# Coprocessor_Board.net
KiCad netlist of a schematic drawn in EAGLE
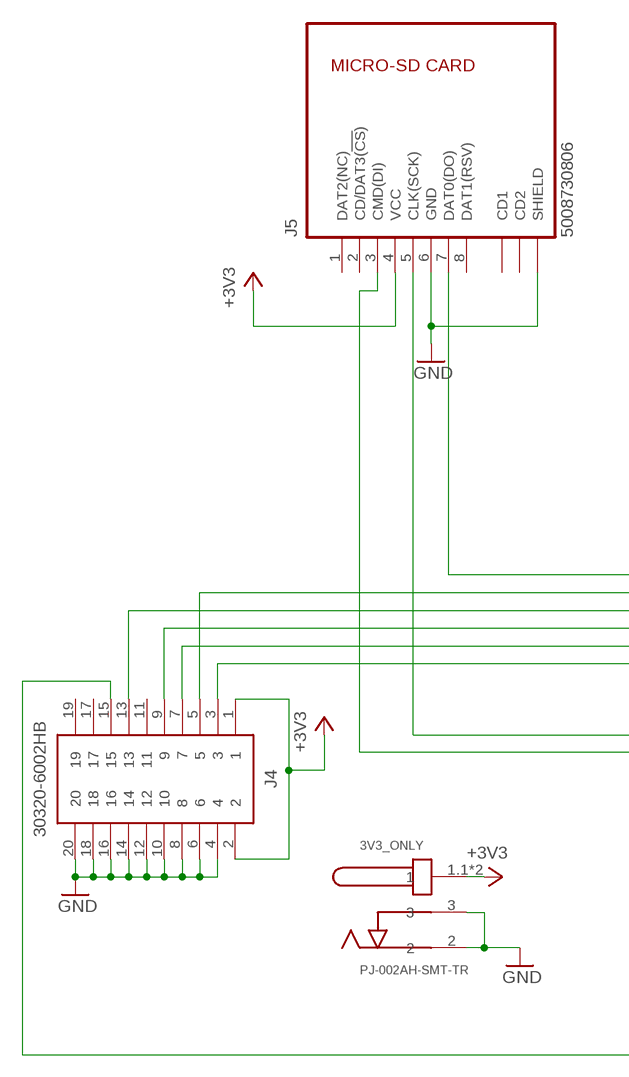
[diagram p0: schematic, sheet 1, part 1 of 2]
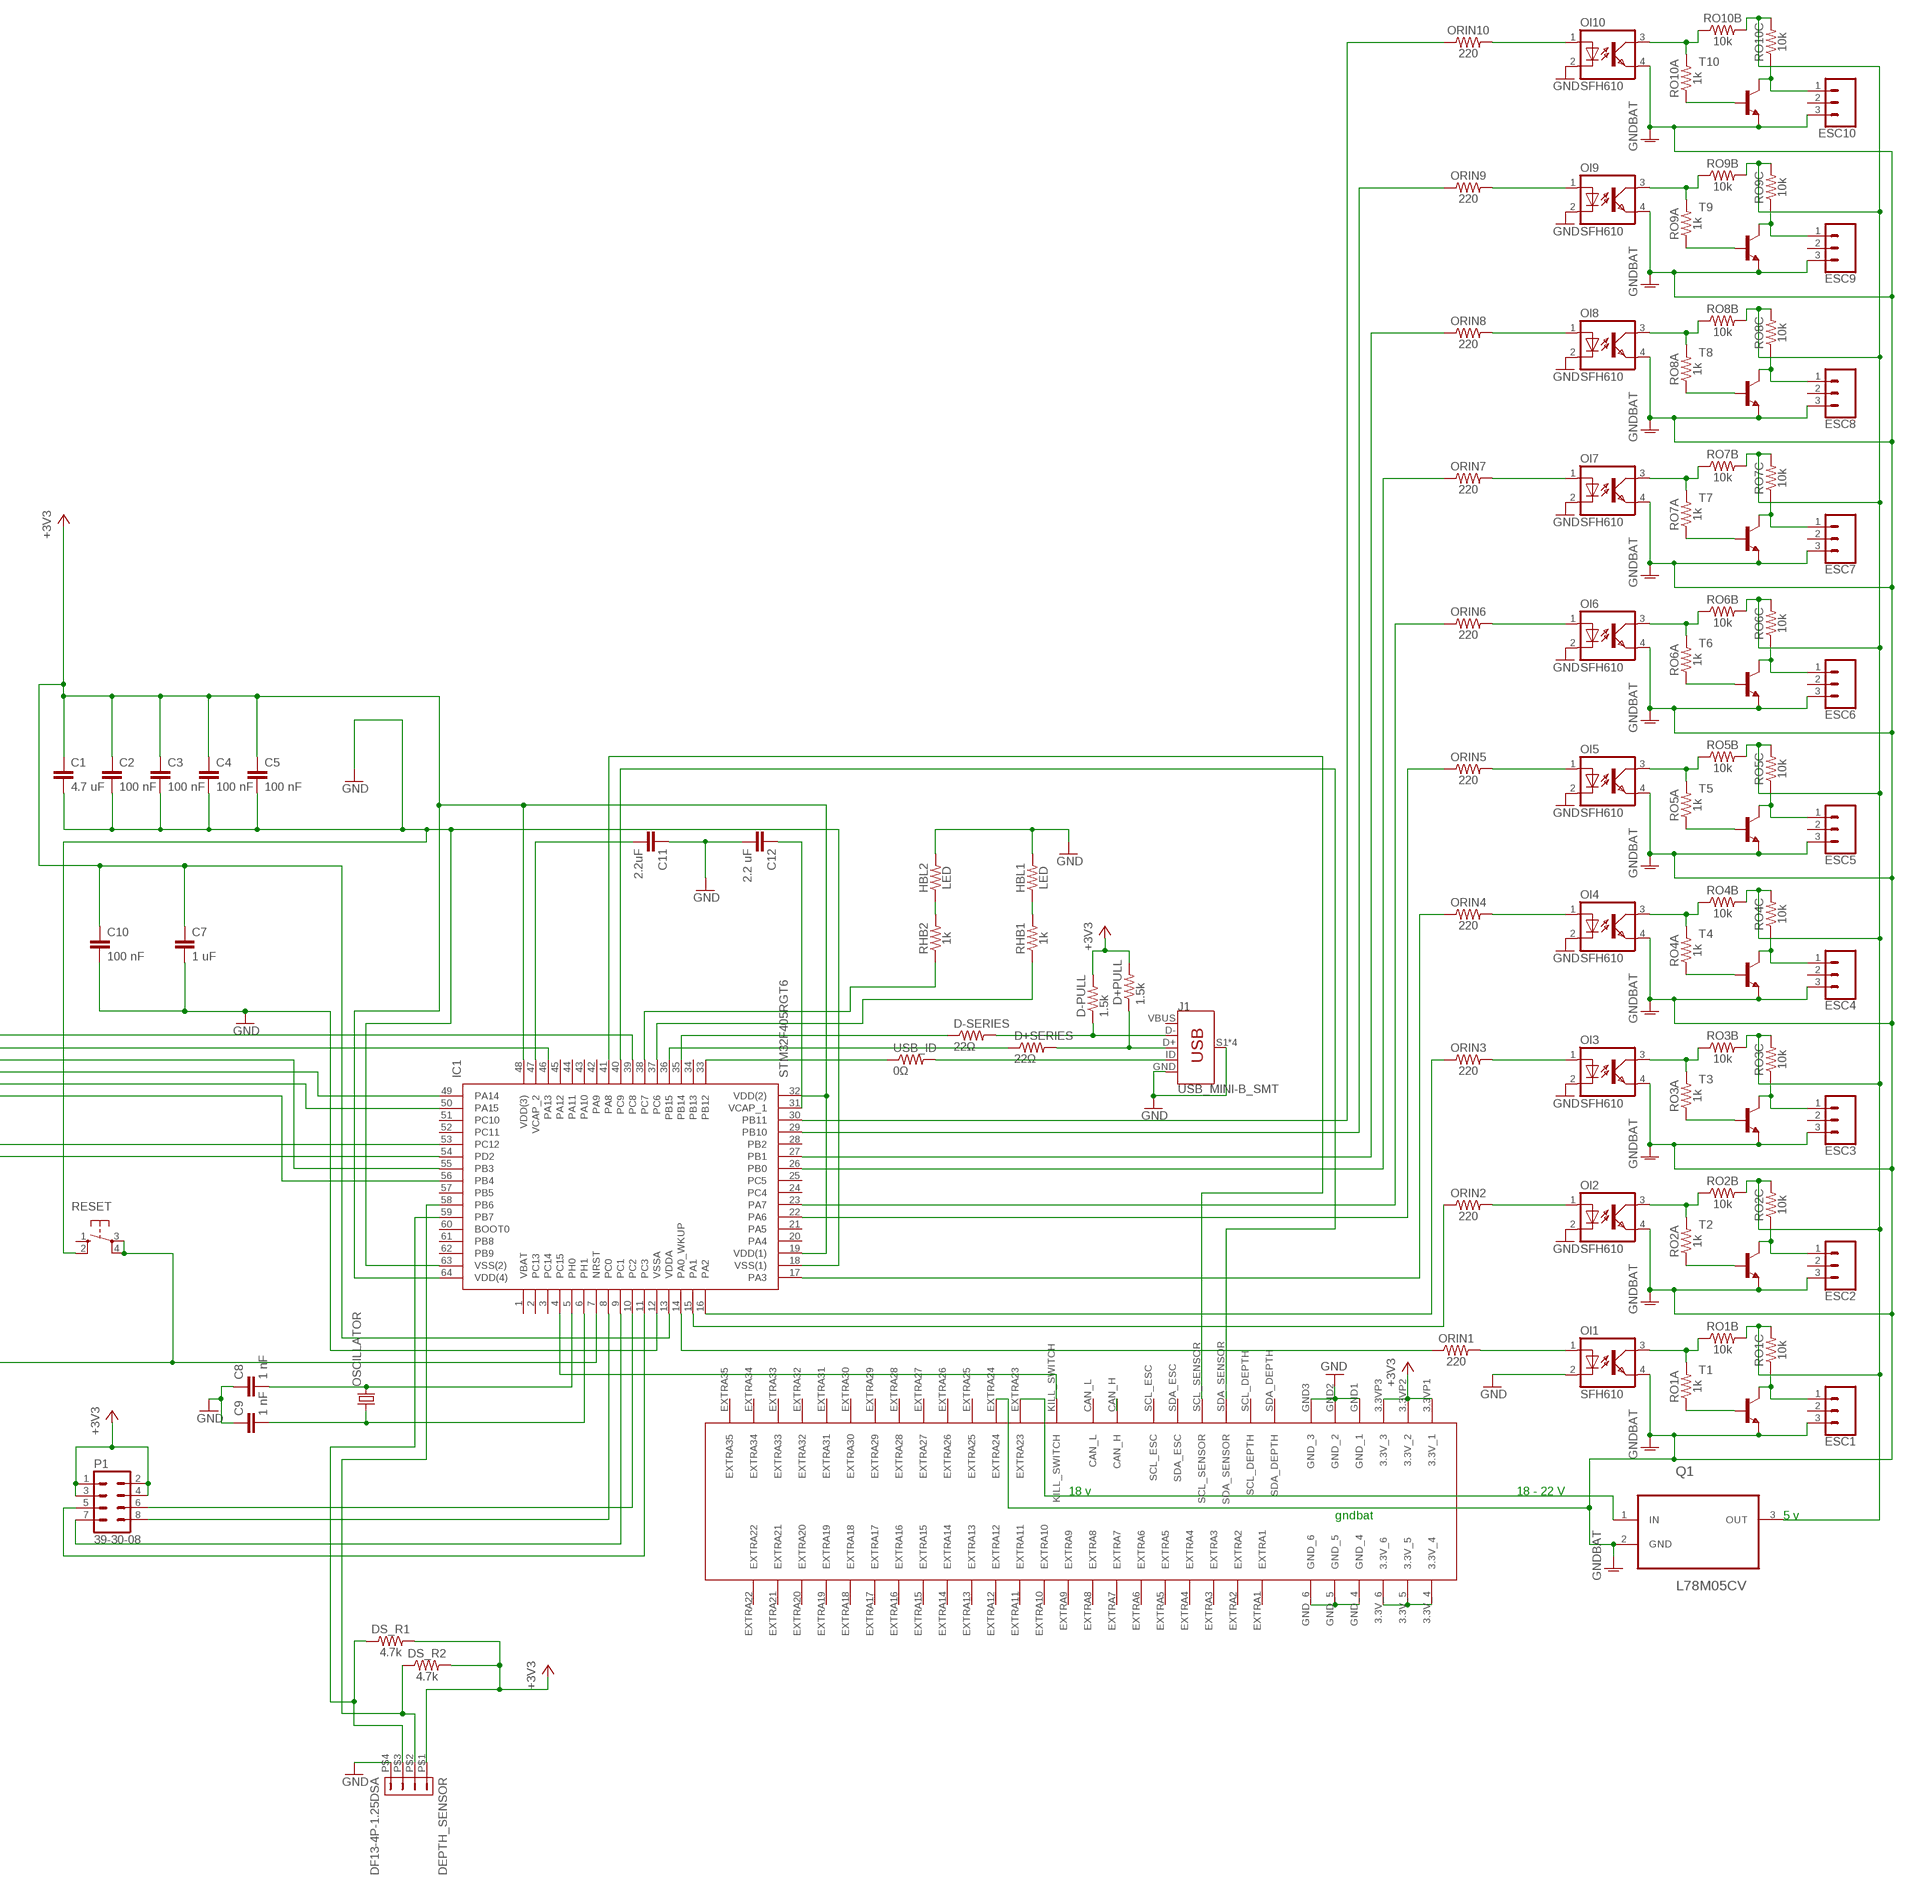
[diagram p1: schematic, sheet 1, part 2 of 2]

(export (version "E")
  (design (tool "Eeschema 10.0.6"))
  (components
    (comp (ref "3V3_ONLY")
      (value "PJ-002AH-SMT-TR")
      (footprint "eagle-import:CUI_PJ-002AH-SMT-TR")
      (fields (field (name "MF") "CUI"))
      (libsource (lib "eagle-import") (part "PJ-002AH-SMT-TR"))
    )
    (comp (ref "C1")
      (value "4.7 uF")
      (footprint "eagle-import:0603")
      (libsource (lib "eagle-import") (part "0.1UF-0603-100V-10%"))
    )
    (comp (ref "C2")
      (value "100 nF")
      (footprint "eagle-import:0603")
      (libsource (lib "eagle-import") (part "0.1UF-0603-100V-10%"))
    )
    (comp (ref "C3")
      (value "100 nF")
      (footprint "eagle-import:0603")
      (libsource (lib "eagle-import") (part "0.1UF-0603-100V-10%"))
    )
    (comp (ref "C4")
      (value "100 nF")
      (footprint "eagle-import:0603")
      (libsource (lib "eagle-import") (part "0.1UF-0603-100V-10%"))
    )
    (comp (ref "C5")
      (value "100 nF")
      (footprint "eagle-import:0603")
      (libsource (lib "eagle-import") (part "0.1UF-0603-100V-10%"))
    )
    (comp (ref "C7")
      (value "1 uF")
      (footprint "eagle-import:0603")
      (libsource (lib "eagle-import") (part "0.1UF-0603-100V-10%"))
    )
    (comp (ref "C8")
      (value "1 nF")
      (footprint "eagle-import:CAP-PTH-2.54")
      (libsource (lib "eagle-import") (part "22PF-PTH-2.54MM-200V-5%"))
    )
    (comp (ref "C9")
      (value "1 nF")
      (footprint "eagle-import:CAP-PTH-2.54")
      (libsource (lib "eagle-import") (part "22PF-PTH-2.54MM-200V-5%"))
    )
    (comp (ref "C10")
      (value "100 nF")
      (footprint "eagle-import:0603")
      (libsource (lib "eagle-import") (part "0.1UF-0603-100V-10%"))
    )
    (comp (ref "C11")
      (value "2.2uF")
      (footprint "eagle-import:0603")
      (libsource (lib "eagle-import") (part "0.1UF-0603-100V-10%"))
    )
    (comp (ref "C12")
      (value "2.2 uF")
      (footprint "eagle-import:0603")
      (libsource (lib "eagle-import") (part "0.1UF-0603-100V-10%"))
    )
    (comp (ref "D+PULL")
      (value "1.5k")
      (footprint "eagle-import:0204_7")
      (libsource (lib "eagle-import") (part "R-US_0204/7"))
    )
    (comp (ref "D+SERIES")
      (value "22Ω")
      (footprint "eagle-import:0204_7")
      (libsource (lib "eagle-import") (part "R-US_0204/7"))
    )
    (comp (ref "D-PULL")
      (value "1.5k")
      (footprint "eagle-import:0204_7")
      (libsource (lib "eagle-import") (part "R-US_0204/7"))
    )
    (comp (ref "D-SERIES")
      (value "22Ω")
      (footprint "eagle-import:0204_7")
      (libsource (lib "eagle-import") (part "R-US_0204/7"))
    )
    (comp (ref "DEPTH_SENSOR")
      (value "DF13-4P-1.25DSA")
      (footprint "eagle-import:DF13-4P-1.25DSA")
      (libsource (lib "eagle-import") (part "DF13-4P-1.25DSA"))
    )
    (comp (ref "DS_R1")
      (value "4.7k")
      (footprint "eagle-import:AXIAL-0.1")
      (libsource (lib "eagle-import") (part "1KOHM-VERT-1/4W-1%"))
    )
    (comp (ref "DS_R2")
      (value "4.7k")
      (footprint "eagle-import:AXIAL-0.1")
      (libsource (lib "eagle-import") (part "1KOHM-VERT-1/4W-1%"))
    )
    (comp (ref "ESC1")
      (value "CONN_03")
      (footprint "eagle-import:1X03")
      (libsource (lib "eagle-import") (part "CONN_03"))
    )
    (comp (ref "ESC2")
      (value "CONN_03")
      (footprint "eagle-import:1X03")
      (libsource (lib "eagle-import") (part "CONN_03"))
    )
    (comp (ref "ESC3")
      (value "CONN_03")
      (footprint "eagle-import:1X03")
      (libsource (lib "eagle-import") (part "CONN_03"))
    )
    (comp (ref "ESC4")
      (value "CONN_03")
      (footprint "eagle-import:1X03")
      (libsource (lib "eagle-import") (part "CONN_03"))
    )
    (comp (ref "ESC5")
      (value "CONN_03")
      (footprint "eagle-import:1X03")
      (libsource (lib "eagle-import") (part "CONN_03"))
    )
    (comp (ref "ESC6")
      (value "CONN_03")
      (footprint "eagle-import:1X03")
      (libsource (lib "eagle-import") (part "CONN_03"))
    )
    (comp (ref "ESC7")
      (value "CONN_03")
      (footprint "eagle-import:1X03")
      (libsource (lib "eagle-import") (part "CONN_03"))
    )
    (comp (ref "ESC8")
      (value "CONN_03")
      (footprint "eagle-import:1X03")
      (libsource (lib "eagle-import") (part "CONN_03"))
    )
    (comp (ref "ESC9")
      (value "CONN_03")
      (footprint "eagle-import:1X03")
      (libsource (lib "eagle-import") (part "CONN_03"))
    )
    (comp (ref "ESC10")
      (value "CONN_03")
      (footprint "eagle-import:1X03")
      (libsource (lib "eagle-import") (part "CONN_03"))
    )
    (comp (ref "HBL1")
      (value "LED")
      (footprint "eagle-import:AXIAL-0.1")
      (libsource (lib "eagle-import") (part "1KOHM-VERT-1/4W-1%"))
    )
    (comp (ref "HBL2")
      (value "LED")
      (footprint "eagle-import:AXIAL-0.1")
      (libsource (lib "eagle-import") (part "1KOHM-VERT-1/4W-1%"))
    )
    (comp (ref "IC1")
      (value "STM32F405RGT6")
      (footprint "eagle-import:QFP50P1200X1200X160-64N")
      (fields (field (name "RS_PART_NUMBER") "7468217"))
      (libsource (lib "eagle-import") (part "STM32F405RGT6"))
    )
    (comp (ref "J1")
      (value "USB_MINI-B_SMT")
      (footprint "eagle-import:USB-MINIB")
      (libsource (lib "eagle-import") (part "USB_MINI-B_SMT"))
    )
    (comp (ref "J4")
      (value "30320-6002HB")
      (footprint "eagle-import:SHDR20W81P254_2X10_3300X840X93")
      (fields (field (name "RS_PART_NUMBER") "8273587"))
      (libsource (lib "eagle-import") (part "30320-6002HB"))
    )
    (comp (ref "J5")
      (value "5008730806")
      (footprint "eagle-import:5008730806")
      (fields (field (name "MF") "Molex") (field (name "MP") "500873-0806"))
      (libsource (lib "eagle-import") (part "5008730806"))
    )
    (comp (ref "OI1")
      (value "SFH610")
      (footprint "eagle-import:DIL04")
      (fields (field (name "MF") "VISHAY/TELEFUNKEN") (field (name "MPN") "SFH6106-4"))
      (libsource (lib "eagle-import") (part "SFH610"))
    )
    (comp (ref "OI2")
      (value "SFH610")
      (footprint "eagle-import:DIL04")
      (fields (field (name "MF") "VISHAY/TELEFUNKEN") (field (name "MPN") "SFH6106-4"))
      (libsource (lib "eagle-import") (part "SFH610"))
    )
    (comp (ref "OI3")
      (value "SFH610")
      (footprint "eagle-import:DIL04")
      (fields (field (name "MF") "VISHAY/TELEFUNKEN") (field (name "MPN") "SFH6106-4"))
      (libsource (lib "eagle-import") (part "SFH610"))
    )
    (comp (ref "OI4")
      (value "SFH610")
      (footprint "eagle-import:DIL04")
      (fields (field (name "MF") "VISHAY/TELEFUNKEN") (field (name "MPN") "SFH6106-4"))
      (libsource (lib "eagle-import") (part "SFH610"))
    )
    (comp (ref "OI5")
      (value "SFH610")
      (footprint "eagle-import:DIL04")
      (fields (field (name "MF") "VISHAY/TELEFUNKEN") (field (name "MPN") "SFH6106-4"))
      (libsource (lib "eagle-import") (part "SFH610"))
    )
    (comp (ref "OI6")
      (value "SFH610")
      (footprint "eagle-import:DIL04")
      (fields (field (name "MF") "VISHAY/TELEFUNKEN") (field (name "MPN") "SFH6106-4"))
      (libsource (lib "eagle-import") (part "SFH610"))
    )
    (comp (ref "OI7")
      (value "SFH610")
      (footprint "eagle-import:DIL04")
      (fields (field (name "MF") "VISHAY/TELEFUNKEN") (field (name "MPN") "SFH6106-4"))
      (libsource (lib "eagle-import") (part "SFH610"))
    )
    (comp (ref "OI8")
      (value "SFH610")
      (footprint "eagle-import:DIL04")
      (fields (field (name "MF") "VISHAY/TELEFUNKEN") (field (name "MPN") "SFH6106-4"))
      (libsource (lib "eagle-import") (part "SFH610"))
    )
    (comp (ref "OI9")
      (value "SFH610")
      (footprint "eagle-import:DIL04")
      (fields (field (name "MF") "VISHAY/TELEFUNKEN") (field (name "MPN") "SFH6106-4"))
      (libsource (lib "eagle-import") (part "SFH610"))
    )
    (comp (ref "OI10")
      (value "SFH610")
      (footprint "eagle-import:DIL04")
      (fields (field (name "MF") "VISHAY/TELEFUNKEN") (field (name "MPN") "SFH6106-4"))
      (libsource (lib "eagle-import") (part "SFH610"))
    )
    (comp (ref "ORIN1")
      (value "220")
      (footprint "eagle-import:AXIAL-0.1")
      (libsource (lib "eagle-import") (part "1KOHM-VERT-1/4W-1%"))
    )
    (comp (ref "ORIN2")
      (value "220")
      (footprint "eagle-import:AXIAL-0.1")
      (libsource (lib "eagle-import") (part "1KOHM-VERT-1/4W-1%"))
    )
    (comp (ref "ORIN3")
      (value "220")
      (footprint "eagle-import:AXIAL-0.1")
      (libsource (lib "eagle-import") (part "1KOHM-VERT-1/4W-1%"))
    )
    (comp (ref "ORIN4")
      (value "220")
      (footprint "eagle-import:AXIAL-0.1")
      (libsource (lib "eagle-import") (part "1KOHM-VERT-1/4W-1%"))
    )
    (comp (ref "ORIN5")
      (value "220")
      (footprint "eagle-import:AXIAL-0.1")
      (libsource (lib "eagle-import") (part "1KOHM-VERT-1/4W-1%"))
    )
    (comp (ref "ORIN6")
      (value "220")
      (footprint "eagle-import:AXIAL-0.1")
      (libsource (lib "eagle-import") (part "1KOHM-VERT-1/4W-1%"))
    )
    (comp (ref "ORIN7")
      (value "220")
      (footprint "eagle-import:AXIAL-0.1")
      (libsource (lib "eagle-import") (part "1KOHM-VERT-1/4W-1%"))
    )
    (comp (ref "ORIN8")
      (value "220")
      (footprint "eagle-import:AXIAL-0.1")
      (libsource (lib "eagle-import") (part "1KOHM-VERT-1/4W-1%"))
    )
    (comp (ref "ORIN9")
      (value "220")
      (footprint "eagle-import:AXIAL-0.1")
      (libsource (lib "eagle-import") (part "1KOHM-VERT-1/4W-1%"))
    )
    (comp (ref "ORIN10")
      (value "220")
      (footprint "eagle-import:AXIAL-0.1")
      (libsource (lib "eagle-import") (part "1KOHM-VERT-1/4W-1%"))
    )
    (comp (ref "OSCILLATOR")
      (value "CRYSTALHC49S")
      (footprint "eagle-import:HC49_S")
      (libsource (lib "eagle-import") (part "CRYSTALHC49S"))
    )
    (comp (ref "P1")
      (value "39-30-08")
      (footprint "eagle-import:39-30-_08_")
      (libsource (lib "eagle-import") (part "39-30-?08?"))
    )
    (comp (ref "Q1")
      (value "L78M05CV")
      (footprint "eagle-import:TO254P450X1020X1935-3P")
      (fields (field (name "MF") "STMicroelectronics"))
      (libsource (lib "eagle-import") (part "L78M05CV"))
    )
    (comp (ref "RESET")
      (value "10-XX")
      (footprint "eagle-import:B3F-10XX")
      (fields (field (name "MPN") "B3F-1000"))
      (libsource (lib "eagle-import") (part "10-XX"))
    )
    (comp (ref "RHB1")
      (value "1k")
      (footprint "eagle-import:AXIAL-0.3")
      (libsource (lib "eagle-import") (part "1KOHM-HORIZ-1/4W-1%"))
    )
    (comp (ref "RHB2")
      (value "1k")
      (footprint "eagle-import:AXIAL-0.3")
      (libsource (lib "eagle-import") (part "1KOHM-HORIZ-1/4W-5%"))
    )
    (comp (ref "RO1A")
      (value "1k")
      (footprint "eagle-import:0603")
      (libsource (lib "eagle-import") (part "1KOHM-0603-1/10W-1%"))
    )
    (comp (ref "RO1B")
      (value "10k")
      (footprint "eagle-import:0603")
      (libsource (lib "eagle-import") (part "1KOHM-0603-1/10W-1%"))
    )
    (comp (ref "RO1C")
      (value "10k")
      (footprint "eagle-import:0603")
      (libsource (lib "eagle-import") (part "1KOHM-0603-1/10W-1%"))
    )
    (comp (ref "RO2A")
      (value "1k")
      (footprint "eagle-import:0603")
      (libsource (lib "eagle-import") (part "1KOHM-0603-1/10W-1%"))
    )
    (comp (ref "RO2B")
      (value "10k")
      (footprint "eagle-import:0603")
      (libsource (lib "eagle-import") (part "1KOHM-0603-1/10W-1%"))
    )
    (comp (ref "RO2C")
      (value "10k")
      (footprint "eagle-import:0603")
      (libsource (lib "eagle-import") (part "1KOHM-0603-1/10W-1%"))
    )
    (comp (ref "RO3A")
      (value "1k")
      (footprint "eagle-import:0603")
      (libsource (lib "eagle-import") (part "1KOHM-0603-1/10W-1%"))
    )
    (comp (ref "RO3B")
      (value "10k")
      (footprint "eagle-import:0603")
      (libsource (lib "eagle-import") (part "1KOHM-0603-1/10W-1%"))
    )
    (comp (ref "RO3C")
      (value "10k")
      (footprint "eagle-import:0603")
      (libsource (lib "eagle-import") (part "1KOHM-0603-1/10W-1%"))
    )
    (comp (ref "RO4A")
      (value "1k")
      (footprint "eagle-import:0603")
      (libsource (lib "eagle-import") (part "1KOHM-0603-1/10W-1%"))
    )
    (comp (ref "RO4B")
      (value "10k")
      (footprint "eagle-import:0603")
      (libsource (lib "eagle-import") (part "1KOHM-0603-1/10W-1%"))
    )
    (comp (ref "RO4C")
      (value "10k")
      (footprint "eagle-import:0603")
      (libsource (lib "eagle-import") (part "1KOHM-0603-1/10W-1%"))
    )
    (comp (ref "RO5A")
      (value "1k")
      (footprint "eagle-import:0603")
      (libsource (lib "eagle-import") (part "1KOHM-0603-1/10W-1%"))
    )
    (comp (ref "RO5B")
      (value "10k")
      (footprint "eagle-import:0603")
      (libsource (lib "eagle-import") (part "1KOHM-0603-1/10W-1%"))
    )
    (comp (ref "RO5C")
      (value "10k")
      (footprint "eagle-import:0603")
      (libsource (lib "eagle-import") (part "1KOHM-0603-1/10W-1%"))
    )
    (comp (ref "RO6A")
      (value "1k")
      (footprint "eagle-import:0603")
      (libsource (lib "eagle-import") (part "1KOHM-0603-1/10W-1%"))
    )
    (comp (ref "RO6B")
      (value "10k")
      (footprint "eagle-import:0603")
      (libsource (lib "eagle-import") (part "1KOHM-0603-1/10W-1%"))
    )
    (comp (ref "RO6C")
      (value "10k")
      (footprint "eagle-import:0603")
      (libsource (lib "eagle-import") (part "1KOHM-0603-1/10W-1%"))
    )
    (comp (ref "RO7A")
      (value "1k")
      (footprint "eagle-import:0603")
      (libsource (lib "eagle-import") (part "1KOHM-0603-1/10W-1%"))
    )
    (comp (ref "RO7B")
      (value "10k")
      (footprint "eagle-import:0603")
      (libsource (lib "eagle-import") (part "1KOHM-0603-1/10W-1%"))
    )
    (comp (ref "RO7C")
      (value "10k")
      (footprint "eagle-import:0603")
      (libsource (lib "eagle-import") (part "1KOHM-0603-1/10W-1%"))
    )
    (comp (ref "RO8A")
      (value "1k")
      (footprint "eagle-import:0603")
      (libsource (lib "eagle-import") (part "1KOHM-0603-1/10W-1%"))
    )
    (comp (ref "RO8B")
      (value "10k")
      (footprint "eagle-import:0603")
      (libsource (lib "eagle-import") (part "1KOHM-0603-1/10W-1%"))
    )
    (comp (ref "RO8C")
      (value "10k")
      (footprint "eagle-import:0603")
      (libsource (lib "eagle-import") (part "1KOHM-0603-1/10W-1%"))
    )
    (comp (ref "RO9A")
      (value "1k")
      (footprint "eagle-import:0603")
      (libsource (lib "eagle-import") (part "1KOHM-0603-1/10W-1%"))
    )
    (comp (ref "RO9B")
      (value "10k")
      (footprint "eagle-import:0603")
      (libsource (lib "eagle-import") (part "1KOHM-0603-1/10W-1%"))
    )
    (comp (ref "RO9C")
      (value "10k")
      (footprint "eagle-import:0603")
      (libsource (lib "eagle-import") (part "1KOHM-0603-1/10W-1%"))
    )
    (comp (ref "RO10A")
      (value "1k")
      (footprint "eagle-import:0603")
      (libsource (lib "eagle-import") (part "1KOHM-0603-1/10W-1%"))
    )
    (comp (ref "RO10B")
      (value "10k")
      (footprint "eagle-import:0603")
      (libsource (lib "eagle-import") (part "1KOHM-0603-1/10W-1%"))
    )
    (comp (ref "RO10C")
      (value "10k")
      (footprint "eagle-import:0603")
      (libsource (lib "eagle-import") (part "1KOHM-0603-1/10W-1%"))
    )
    (comp (ref "T1")
      (value "-NPN-TO126V")
      (footprint "eagle-import:TO126V")
      (libsource (lib "eagle-import") (part "-NPN-TO126V"))
    )
    (comp (ref "T2")
      (value "-NPN-TO126V")
      (footprint "eagle-import:TO126V")
      (libsource (lib "eagle-import") (part "-NPN-TO126V"))
    )
    (comp (ref "T3")
      (value "-NPN-TO126V")
      (footprint "eagle-import:TO126V")
      (libsource (lib "eagle-import") (part "-NPN-TO126V"))
    )
    (comp (ref "T4")
      (value "-NPN-TO126V")
      (footprint "eagle-import:TO126V")
      (libsource (lib "eagle-import") (part "-NPN-TO126V"))
    )
    (comp (ref "T5")
      (value "-NPN-TO126V")
      (footprint "eagle-import:TO126V")
      (libsource (lib "eagle-import") (part "-NPN-TO126V"))
    )
    (comp (ref "T6")
      (value "-NPN-TO126V")
      (footprint "eagle-import:TO126V")
      (libsource (lib "eagle-import") (part "-NPN-TO126V"))
    )
    (comp (ref "T7")
      (value "-NPN-TO126V")
      (footprint "eagle-import:TO126V")
      (libsource (lib "eagle-import") (part "-NPN-TO126V"))
    )
    (comp (ref "T8")
      (value "-NPN-TO126V")
      (footprint "eagle-import:TO126V")
      (libsource (lib "eagle-import") (part "-NPN-TO126V"))
    )
    (comp (ref "T9")
      (value "-NPN-TO126V")
      (footprint "eagle-import:TO126V")
      (libsource (lib "eagle-import") (part "-NPN-TO126V"))
    )
    (comp (ref "T10")
      (value "-NPN-TO126V")
      (footprint "eagle-import:TO126V")
      (libsource (lib "eagle-import") (part "-NPN-TO126V"))
    )
    (comp (ref "U$1")
      (value "5530843")
      (footprint "eagle-import:5530843-6-BOARDFINGERS")
      (libsource (lib "eagle-import") (part "5530843"))
    )
    (comp (ref "USB_ID")
      (value "0Ω")
      (footprint "eagle-import:0204_7")
      (libsource (lib "eagle-import") (part "R-US_0204/7"))
    )
  )
  (nets
    (net (code "1") (name "+3V3") (class "Default")
      (node (ref "3V3_ONLY") (pin "1.1") (pinfunction "1_1.1") (pintype "passive"))
      (node (ref "3V3_ONLY") (pin "1.2") (pinfunction "1_1.2") (pintype "passive"))
      (node (ref "C1") (pin "1") (pinfunction "1_1") (pintype "passive"))
      (node (ref "C10") (pin "1") (pinfunction "1_1") (pintype "passive"))
      (node (ref "C2") (pin "1") (pinfunction "1_1") (pintype "passive"))
      (node (ref "C3") (pin "1") (pinfunction "1_1") (pintype "passive"))
      (node (ref "C4") (pin "1") (pinfunction "1_1") (pintype "passive"))
      (node (ref "C5") (pin "1") (pinfunction "1_1") (pintype "passive"))
      (node (ref "C7") (pin "1") (pinfunction "1_1") (pintype "passive"))
      (node (ref "D+PULL") (pin "2") (pinfunction "2_2") (pintype "passive"))
      (node (ref "D-PULL") (pin "2") (pinfunction "2_2") (pintype "passive"))
      (node (ref "DEPTH_SENSOR") (pin "P$1") (pinfunction "1_P$1") (pintype "passive"))
      (node (ref "DS_R1") (pin "P$2") (pinfunction "2_P$2") (pintype "passive"))
      (node (ref "DS_R2") (pin "P$2") (pinfunction "2_P$2") (pintype "passive"))
      (node (ref "IC1") (pin "13") (pinfunction "VDDA_13") (pintype "power_in"))
      (node (ref "IC1") (pin "19") (pinfunction "VDD(1)_19") (pintype "power_in"))
      (node (ref "IC1") (pin "32") (pinfunction "VDD(2)_32") (pintype "power_in"))
      (node (ref "IC1") (pin "48") (pinfunction "VDD(3)_48") (pintype "power_in"))
      (node (ref "IC1") (pin "64") (pinfunction "VDD(4)_64") (pintype "power_in"))
      (node (ref "J4") (pin "1") (pinfunction "1_1") (pintype "passive"))
      (node (ref "J4") (pin "2") (pinfunction "2_2") (pintype "passive"))
      (node (ref "J5") (pin "4") (pinfunction "VCC_4") (pintype "bidirectional"))
      (node (ref "P1") (pin "1") (pinfunction "1_1") (pintype "passive"))
      (node (ref "P1") (pin "2") (pinfunction "2_2") (pintype "passive"))
      (node (ref "P1") (pin "3") (pinfunction "3_3") (pintype "passive"))
      (node (ref "P1") (pin "4") (pinfunction "4_4") (pintype "passive"))
      (node (ref "U$1") (pin "3.3VP1") (pinfunction "3.3V_1_3.3VP1") (pintype "bidirectional"))
      (node (ref "U$1") (pin "3.3VP2") (pinfunction "3.3V_2_3.3VP2") (pintype "bidirectional"))
      (node (ref "U$1") (pin "3.3VP3") (pinfunction "3.3V_3_3.3VP3") (pintype "bidirectional"))
      (node (ref "U$1") (pin "3.3V_4") (pinfunction "3.3V_4_3.3V_4") (pintype "bidirectional"))
      (node (ref "U$1") (pin "3.3V_5") (pinfunction "3.3V_5_3.3V_5") (pintype "bidirectional"))
      (node (ref "U$1") (pin "3.3V_6") (pinfunction "3.3V_6_3.3V_6") (pintype "bidirectional"))
    )
    (net (code "2") (name "/VBUS") (class "Default")
      (node (ref "J1") (pin "VBUS") (pinfunction "VBUS_VBUS") (pintype "power_in"))
    )
    (net (code "3") (name "GND") (class "Default")
      (node (ref "3V3_ONLY") (pin "2") (pinfunction "2_2") (pintype "passive"))
      (node (ref "3V3_ONLY") (pin "3") (pinfunction "3_3") (pintype "passive"))
      (node (ref "C1") (pin "2") (pinfunction "2_2") (pintype "passive"))
      (node (ref "C10") (pin "2") (pinfunction "2_2") (pintype "passive"))
      (node (ref "C11") (pin "1") (pinfunction "1_1") (pintype "passive"))
      (node (ref "C12") (pin "2") (pinfunction "2_2") (pintype "passive"))
      (node (ref "C2") (pin "2") (pinfunction "2_2") (pintype "passive"))
      (node (ref "C3") (pin "2") (pinfunction "2_2") (pintype "passive"))
      (node (ref "C4") (pin "2") (pinfunction "2_2") (pintype "passive"))
      (node (ref "C5") (pin "2") (pinfunction "2_2") (pintype "passive"))
      (node (ref "C7") (pin "2") (pinfunction "2_2") (pintype "passive"))
      (node (ref "C8") (pin "1") (pinfunction "1_1") (pintype "passive"))
      (node (ref "C9") (pin "1") (pinfunction "1_1") (pintype "passive"))
      (node (ref "DEPTH_SENSOR") (pin "P$4") (pinfunction "4_P$4") (pintype "passive"))
      (node (ref "HBL1") (pin "P$2") (pinfunction "2_P$2") (pintype "passive"))
      (node (ref "HBL2") (pin "P$2") (pinfunction "2_P$2") (pintype "passive"))
      (node (ref "IC1") (pin "12") (pinfunction "VSSA_12") (pintype "power_in"))
      (node (ref "IC1") (pin "18") (pinfunction "VSS(1)_18") (pintype "power_in"))
      (node (ref "IC1") (pin "63") (pinfunction "VSS(2)_63") (pintype "power_in"))
      (node (ref "J1") (pin "GND") (pinfunction "GND_GND") (pintype "power_in"))
      (node (ref "J1") (pin "S1") (pinfunction "SHIELD_S1") (pintype "bidirectional"))
      (node (ref "J1") (pin "S2") (pinfunction "SHIELD_S2") (pintype "bidirectional"))
      (node (ref "J1") (pin "S3") (pinfunction "SHIELD_S3") (pintype "bidirectional"))
      (node (ref "J1") (pin "S4") (pinfunction "SHIELD_S4") (pintype "bidirectional"))
      (node (ref "J4") (pin "10") (pinfunction "10_10") (pintype "passive"))
      (node (ref "J4") (pin "12") (pinfunction "12_12") (pintype "passive"))
      (node (ref "J4") (pin "14") (pinfunction "14_14") (pintype "passive"))
      (node (ref "J4") (pin "16") (pinfunction "16_16") (pintype "passive"))
      (node (ref "J4") (pin "18") (pinfunction "18_18") (pintype "passive"))
      (node (ref "J4") (pin "20") (pinfunction "20_20") (pintype "passive"))
      (node (ref "J4") (pin "4") (pinfunction "4_4") (pintype "passive"))
      (node (ref "J4") (pin "6") (pinfunction "6_6") (pintype "passive"))
      (node (ref "J4") (pin "8") (pinfunction "8_8") (pintype "passive"))
      (node (ref "J5") (pin "6") (pinfunction "GND_6") (pintype "bidirectional"))
      (node (ref "J5") (pin "S3") (pinfunction "SHIELD_S3") (pintype "bidirectional"))
      (node (ref "J5") (pin "S4") (pinfunction "SHIELD_S4") (pintype "bidirectional"))
      (node (ref "OI1") (pin "2") (pinfunction "C_2") (pintype "passive"))
      (node (ref "OI10") (pin "2") (pinfunction "C_2") (pintype "passive"))
      (node (ref "OI2") (pin "2") (pinfunction "C_2") (pintype "passive"))
      (node (ref "OI3") (pin "2") (pinfunction "C_2") (pintype "passive"))
      (node (ref "OI4") (pin "2") (pinfunction "C_2") (pintype "passive"))
      (node (ref "OI5") (pin "2") (pinfunction "C_2") (pintype "passive"))
      (node (ref "OI6") (pin "2") (pinfunction "C_2") (pintype "passive"))
      (node (ref "OI7") (pin "2") (pinfunction "C_2") (pintype "passive"))
      (node (ref "OI8") (pin "2") (pinfunction "C_2") (pintype "passive"))
      (node (ref "OI9") (pin "2") (pinfunction "C_2") (pintype "passive"))
      (node (ref "RESET") (pin "2") (pinfunction "S1_2") (pintype "passive"))
      (node (ref "U$1") (pin "GND1") (pinfunction "GND_1_GND1") (pintype "bidirectional"))
      (node (ref "U$1") (pin "GND2") (pinfunction "GND_2_GND2") (pintype "bidirectional"))
      (node (ref "U$1") (pin "GND3") (pinfunction "GND_3_GND3") (pintype "bidirectional"))
      (node (ref "U$1") (pin "GND_4") (pinfunction "GND_4_GND_4") (pintype "bidirectional"))
      (node (ref "U$1") (pin "GND_5") (pinfunction "GND_5_GND_5") (pintype "bidirectional"))
      (node (ref "U$1") (pin "GND_6") (pinfunction "GND_6_GND_6") (pintype "bidirectional"))
    )
    (net (code "4") (name "GNDBAT") (class "Default")
      (node (ref "ESC1") (pin "3") (pinfunction "3_3") (pintype "passive"))
      (node (ref "ESC10") (pin "3") (pinfunction "3_3") (pintype "passive"))
      (node (ref "ESC2") (pin "3") (pinfunction "3_3") (pintype "passive"))
      (node (ref "ESC3") (pin "3") (pinfunction "3_3") (pintype "passive"))
      (node (ref "ESC4") (pin "3") (pinfunction "3_3") (pintype "passive"))
      (node (ref "ESC5") (pin "3") (pinfunction "3_3") (pintype "passive"))
      (node (ref "ESC6") (pin "3") (pinfunction "3_3") (pintype "passive"))
      (node (ref "ESC7") (pin "3") (pinfunction "3_3") (pintype "passive"))
      (node (ref "ESC8") (pin "3") (pinfunction "3_3") (pintype "passive"))
      (node (ref "ESC9") (pin "3") (pinfunction "3_3") (pintype "passive"))
      (node (ref "OI1") (pin "4") (pinfunction "EMIT_4") (pintype "passive"))
      (node (ref "OI10") (pin "4") (pinfunction "EMIT_4") (pintype "passive"))
      (node (ref "OI2") (pin "4") (pinfunction "EMIT_4") (pintype "passive"))
      (node (ref "OI3") (pin "4") (pinfunction "EMIT_4") (pintype "passive"))
      (node (ref "OI4") (pin "4") (pinfunction "EMIT_4") (pintype "passive"))
      (node (ref "OI5") (pin "4") (pinfunction "EMIT_4") (pintype "passive"))
      (node (ref "OI6") (pin "4") (pinfunction "EMIT_4") (pintype "passive"))
      (node (ref "OI7") (pin "4") (pinfunction "EMIT_4") (pintype "passive"))
      (node (ref "OI8") (pin "4") (pinfunction "EMIT_4") (pintype "passive"))
      (node (ref "OI9") (pin "4") (pinfunction "EMIT_4") (pintype "passive"))
      (node (ref "Q1") (pin "2") (pinfunction "GND_2") (pintype "passive"))
      (node (ref "T1") (pin "1") (pinfunction "E_1") (pintype "passive"))
      (node (ref "T10") (pin "1") (pinfunction "E_1") (pintype "passive"))
      (node (ref "T2") (pin "1") (pinfunction "E_1") (pintype "passive"))
      (node (ref "T3") (pin "1") (pinfunction "E_1") (pintype "passive"))
      (node (ref "T4") (pin "1") (pinfunction "E_1") (pintype "passive"))
      (node (ref "T5") (pin "1") (pinfunction "E_1") (pintype "passive"))
      (node (ref "T6") (pin "1") (pinfunction "E_1") (pintype "passive"))
      (node (ref "T7") (pin "1") (pinfunction "E_1") (pintype "passive"))
      (node (ref "T8") (pin "1") (pinfunction "E_1") (pintype "passive"))
      (node (ref "T9") (pin "1") (pinfunction "E_1") (pintype "passive"))
      (node (ref "U$1") (pin "EXTRA24") (pinfunction "EXTRA24_EXTRA24") (pintype "bidirectional"))
    )
    (net (code "5") (name "Net-(D+PULL-Pad1)") (class "Default")
      (node (ref "D+PULL") (pin "1") (pinfunction "1_1") (pintype "passive"))
      (node (ref "D+SERIES") (pin "2") (pinfunction "2_2") (pintype "passive"))
      (node (ref "J1") (pin "D+") (pinfunction "D+_D+") (pintype "bidirectional"))
    )
    (net (code "6") (name "Net-(D-PULL-Pad1)") (class "Default")
      (node (ref "D-PULL") (pin "1") (pinfunction "1_1") (pintype "passive"))
      (node (ref "D-SERIES") (pin "2") (pinfunction "2_2") (pintype "passive"))
      (node (ref "J1") (pin "D-") (pinfunction "D-_D-") (pintype "bidirectional"))
    )
    (net (code "7") (name "Net-(DEPTH_SENSOR-2)") (class "Default")
      (node (ref "DEPTH_SENSOR") (pin "P$2") (pinfunction "2_P$2") (pintype "passive"))
      (node (ref "DS_R2") (pin "P$1") (pinfunction "1_P$1") (pintype "passive"))
      (node (ref "IC1") (pin "58") (pinfunction "PB6_58") (pintype "passive"))
    )
    (net (code "8") (name "Net-(DEPTH_SENSOR-3)") (class "Default")
      (node (ref "DEPTH_SENSOR") (pin "P$3") (pinfunction "3_P$3") (pintype "passive"))
      (node (ref "DS_R1") (pin "P$1") (pinfunction "1_P$1") (pintype "passive"))
      (node (ref "IC1") (pin "59") (pinfunction "PB7_59") (pintype "passive"))
    )
    (net (code "9") (name "Net-(HBL1-1)") (class "Default")
      (node (ref "HBL1") (pin "P$1") (pinfunction "1_P$1") (pintype "passive"))
      (node (ref "RHB1") (pin "P$2") (pinfunction "2_P$2") (pintype "passive"))
    )
    (net (code "10") (name "Net-(HBL2-1)") (class "Default")
      (node (ref "HBL2") (pin "P$1") (pinfunction "1_P$1") (pintype "passive"))
      (node (ref "RHB2") (pin "P$2") (pinfunction "2_P$2") (pintype "passive"))
    )
    (net (code "11") (name "Net-(IC1-NRST)") (class "Default")
      (node (ref "IC1") (pin "7") (pinfunction "NRST_7") (pintype "input"))
      (node (ref "J4") (pin "15") (pinfunction "15_15") (pintype "passive"))
      (node (ref "RESET") (pin "3") (pinfunction "P_3") (pintype "passive"))
      (node (ref "RESET") (pin "4") (pinfunction "P1_4") (pintype "passive"))
    )
    (net (code "12") (name "Net-(IC1-PA0_WKUP)") (class "Default")
      (node (ref "IC1") (pin "14") (pinfunction "PA0_WKUP_14") (pintype "passive"))
      (node (ref "ORIN1") (pin "P$1") (pinfunction "1_P$1") (pintype "passive"))
    )
    (net (code "13") (name "Net-(IC1-PA1)") (class "Default")
      (node (ref "IC1") (pin "15") (pinfunction "PA1_15") (pintype "passive"))
      (node (ref "ORIN2") (pin "P$1") (pinfunction "1_P$1") (pintype "passive"))
    )
    (net (code "14") (name "Net-(IC1-PA2)") (class "Default")
      (node (ref "IC1") (pin "16") (pinfunction "PA2_16") (pintype "passive"))
      (node (ref "ORIN3") (pin "P$1") (pinfunction "1_P$1") (pintype "passive"))
    )
    (net (code "15") (name "Net-(IC1-PA3)") (class "Default")
      (node (ref "IC1") (pin "17") (pinfunction "PA3_17") (pintype "passive"))
      (node (ref "ORIN4") (pin "P$1") (pinfunction "1_P$1") (pintype "passive"))
    )
    (net (code "16") (name "Net-(IC1-PA6)") (class "Default")
      (node (ref "IC1") (pin "22") (pinfunction "PA6_22") (pintype "passive"))
      (node (ref "ORIN5") (pin "P$1") (pinfunction "1_P$1") (pintype "passive"))
    )
    (net (code "17") (name "Net-(IC1-PA7)") (class "Default")
      (node (ref "IC1") (pin "23") (pinfunction "PA7_23") (pintype "passive"))
      (node (ref "ORIN6") (pin "P$1") (pinfunction "1_P$1") (pintype "passive"))
    )
    (net (code "18") (name "Net-(IC1-PA8)") (class "Default")
      (node (ref "IC1") (pin "41") (pinfunction "PA8_41") (pintype "passive"))
      (node (ref "U$1") (pin "SCL_SENSOR") (pinfunction "SCL_SENSOR_SCL_SENSOR") (pintype "bidirectional"))
    )
    (net (code "19") (name "Net-(IC1-PA13)") (class "Default")
      (node (ref "IC1") (pin "46") (pinfunction "PA13_46") (pintype "passive"))
      (node (ref "J4") (pin "5") (pinfunction "5_5") (pintype "passive"))
    )
    (net (code "20") (name "Net-(IC1-PA14)") (class "Default")
      (node (ref "IC1") (pin "49") (pinfunction "PA14_49") (pintype "passive"))
      (node (ref "J4") (pin "9") (pinfunction "9_9") (pintype "passive"))
    )
    (net (code "21") (name "Net-(IC1-PA15)") (class "Default")
      (node (ref "IC1") (pin "50") (pinfunction "PA15_50") (pintype "passive"))
      (node (ref "J4") (pin "7") (pinfunction "7_7") (pintype "passive"))
    )
    (net (code "22") (name "Net-(IC1-PB0)") (class "Default")
      (node (ref "IC1") (pin "26") (pinfunction "PB0_26") (pintype "passive"))
      (node (ref "ORIN7") (pin "P$1") (pinfunction "1_P$1") (pintype "passive"))
    )
    (net (code "23") (name "Net-(IC1-PB1)") (class "Default")
      (node (ref "IC1") (pin "27") (pinfunction "PB1_27") (pintype "passive"))
      (node (ref "ORIN8") (pin "P$1") (pinfunction "1_P$1") (pintype "passive"))
    )
    (net (code "24") (name "Net-(IC1-PB3)") (class "Default")
      (node (ref "IC1") (pin "55") (pinfunction "PB3_55") (pintype "passive"))
      (node (ref "J4") (pin "13") (pinfunction "13_13") (pintype "passive"))
    )
    (net (code "25") (name "Net-(IC1-PB4)") (class "Default")
      (node (ref "IC1") (pin "56") (pinfunction "PB4_56") (pintype "passive"))
      (node (ref "J4") (pin "3") (pinfunction "3_3") (pintype "passive"))
    )
    (net (code "26") (name "Net-(IC1-PB10)") (class "Default")
      (node (ref "IC1") (pin "29") (pinfunction "PB10_29") (pintype "passive"))
      (node (ref "ORIN9") (pin "P$1") (pinfunction "1_P$1") (pintype "passive"))
    )
    (net (code "27") (name "Net-(IC1-PB11)") (class "Default")
      (node (ref "IC1") (pin "30") (pinfunction "PB11_30") (pintype "passive"))
      (node (ref "ORIN10") (pin "P$1") (pinfunction "1_P$1") (pintype "passive"))
    )
    (net (code "28") (name "Net-(IC1-PB12)") (class "Default")
      (node (ref "IC1") (pin "33") (pinfunction "PB12_33") (pintype "passive"))
      (node (ref "USB_ID") (pin "1") (pinfunction "1_1") (pintype "passive"))
    )
    (net (code "29") (name "Net-(IC1-PB14)") (class "Default")
      (node (ref "D-SERIES") (pin "1") (pinfunction "1_1") (pintype "passive"))
      (node (ref "IC1") (pin "35") (pinfunction "PB14_35") (pintype "passive"))
    )
    (net (code "30") (name "Net-(IC1-PB15)") (class "Default")
      (node (ref "D+SERIES") (pin "1") (pinfunction "1_1") (pintype "passive"))
      (node (ref "IC1") (pin "36") (pinfunction "PB15_36") (pintype "passive"))
    )
    (net (code "31") (name "Net-(IC1-PC0)") (class "Default")
      (node (ref "IC1") (pin "8") (pinfunction "PC0_8") (pintype "passive"))
      (node (ref "P1") (pin "8") (pinfunction "8_8") (pintype "passive"))
    )
    (net (code "32") (name "Net-(IC1-PC1)") (class "Default")
      (node (ref "IC1") (pin "9") (pinfunction "PC1_9") (pintype "passive"))
      (node (ref "P1") (pin "7") (pinfunction "7_7") (pintype "passive"))
    )
    (net (code "33") (name "Net-(IC1-PC2)") (class "Default")
      (node (ref "IC1") (pin "10") (pinfunction "PC2_10") (pintype "passive"))
      (node (ref "P1") (pin "6") (pinfunction "6_6") (pintype "passive"))
    )
    (net (code "34") (name "Net-(IC1-PC3)") (class "Default")
      (node (ref "IC1") (pin "11") (pinfunction "PC3_11") (pintype "passive"))
      (node (ref "P1") (pin "5") (pinfunction "5_5") (pintype "passive"))
    )
    (net (code "35") (name "Net-(IC1-PC6)") (class "Default")
      (node (ref "IC1") (pin "37") (pinfunction "PC6_37") (pintype "passive"))
      (node (ref "RHB1") (pin "P$1") (pinfunction "1_P$1") (pintype "passive"))
    )
    (net (code "36") (name "Net-(IC1-PC7)") (class "Default")
      (node (ref "IC1") (pin "38") (pinfunction "PC7_38") (pintype "passive"))
      (node (ref "RHB2") (pin "P$1") (pinfunction "1_P$1") (pintype "passive"))
    )
    (net (code "37") (name "Net-(IC1-PC8)") (class "Default")
      (node (ref "IC1") (pin "39") (pinfunction "PC8_39") (pintype "passive"))
      (node (ref "J5") (pin "7") (pinfunction "DAT0(DO)_7") (pintype "bidirectional"))
    )
    (net (code "38") (name "Net-(IC1-PC9)") (class "Default")
      (node (ref "IC1") (pin "40") (pinfunction "PC9_40") (pintype "passive"))
      (node (ref "U$1") (pin "SDA_SENSOR") (pinfunction "SDA_SENSOR_SDA_SENSOR") (pintype "bidirectional"))
    )
    (net (code "39") (name "Net-(IC1-PC12)") (class "Default")
      (node (ref "IC1") (pin "53") (pinfunction "PC12_53") (pintype "passive"))
      (node (ref "J5") (pin "5") (pinfunction "CLK(SCK)_5") (pintype "bidirectional"))
    )
    (net (code "40") (name "Net-(IC1-PC15)") (class "Default")
      (node (ref "IC1") (pin "4") (pinfunction "PC15_4") (pintype "passive"))
      (node (ref "U$1") (pin "KILL_SWITCH") (pinfunction "KILL_SWITCH_KILL_SWITCH") (pintype "bidirectional"))
    )
    (net (code "41") (name "Net-(IC1-PD2)") (class "Default")
      (node (ref "IC1") (pin "54") (pinfunction "PD2_54") (pintype "passive"))
      (node (ref "J5") (pin "3") (pinfunction "CMD(DI)_3") (pintype "bidirectional"))
    )
    (net (code "42") (name "Net-(IC1-PH0)") (class "Default")
      (node (ref "C8") (pin "2") (pinfunction "2_2") (pintype "passive"))
      (node (ref "IC1") (pin "5") (pinfunction "PH0_5") (pintype "passive"))
      (node (ref "OSCILLATOR") (pin "2") (pinfunction "2_2") (pintype "passive"))
    )
    (net (code "43") (name "Net-(IC1-PH1)") (class "Default")
      (node (ref "C9") (pin "2") (pinfunction "2_2") (pintype "passive"))
      (node (ref "IC1") (pin "6") (pinfunction "PH1_6") (pintype "passive"))
      (node (ref "OSCILLATOR") (pin "1") (pinfunction "1_1") (pintype "passive"))
    )
    (net (code "44") (name "Net-(IC1-VCAP_1)") (class "Default")
      (node (ref "C12") (pin "1") (pinfunction "1_1") (pintype "passive"))
      (node (ref "IC1") (pin "31") (pinfunction "VCAP_1_31") (pintype "passive"))
    )
    (net (code "45") (name "Net-(IC1-VCAP_2)") (class "Default")
      (node (ref "C11") (pin "2") (pinfunction "2_2") (pintype "passive"))
      (node (ref "IC1") (pin "47") (pinfunction "VCAP_2_47") (pintype "passive"))
    )
    (net (code "46") (name "Net-(J1-PadID)") (class "Default")
      (node (ref "J1") (pin "ID") (pinfunction "ID_ID") (pintype "bidirectional"))
      (node (ref "USB_ID") (pin "2") (pinfunction "2_2") (pintype "passive"))
    )
    (net (code "47") (name "Net-(OI1-A)") (class "Default")
      (node (ref "OI1") (pin "1") (pinfunction "A_1") (pintype "passive"))
      (node (ref "ORIN1") (pin "P$2") (pinfunction "2_P$2") (pintype "passive"))
    )
    (net (code "48") (name "Net-(OI1-COL)") (class "Default")
      (node (ref "OI1") (pin "3") (pinfunction "COL_3") (pintype "passive"))
      (node (ref "RO1A") (pin "2") (pinfunction "2_2") (pintype "passive"))
      (node (ref "RO1B") (pin "1") (pinfunction "1_1") (pintype "passive"))
    )
    (net (code "49") (name "Net-(OI2-A)") (class "Default")
      (node (ref "OI2") (pin "1") (pinfunction "A_1") (pintype "passive"))
      (node (ref "ORIN2") (pin "P$2") (pinfunction "2_P$2") (pintype "passive"))
    )
    (net (code "50") (name "Net-(OI2-COL)") (class "Default")
      (node (ref "OI2") (pin "3") (pinfunction "COL_3") (pintype "passive"))
      (node (ref "RO2A") (pin "2") (pinfunction "2_2") (pintype "passive"))
      (node (ref "RO2B") (pin "1") (pinfunction "1_1") (pintype "passive"))
    )
    (net (code "51") (name "Net-(OI3-A)") (class "Default")
      (node (ref "OI3") (pin "1") (pinfunction "A_1") (pintype "passive"))
      (node (ref "ORIN3") (pin "P$2") (pinfunction "2_P$2") (pintype "passive"))
    )
    (net (code "52") (name "Net-(OI3-COL)") (class "Default")
      (node (ref "OI3") (pin "3") (pinfunction "COL_3") (pintype "passive"))
      (node (ref "RO3A") (pin "2") (pinfunction "2_2") (pintype "passive"))
      (node (ref "RO3B") (pin "1") (pinfunction "1_1") (pintype "passive"))
    )
    (net (code "53") (name "Net-(OI4-A)") (class "Default")
      (node (ref "OI4") (pin "1") (pinfunction "A_1") (pintype "passive"))
      (node (ref "ORIN4") (pin "P$2") (pinfunction "2_P$2") (pintype "passive"))
    )
    (net (code "54") (name "Net-(OI4-COL)") (class "Default")
      (node (ref "OI4") (pin "3") (pinfunction "COL_3") (pintype "passive"))
      (node (ref "RO4A") (pin "2") (pinfunction "2_2") (pintype "passive"))
      (node (ref "RO4B") (pin "1") (pinfunction "1_1") (pintype "passive"))
    )
    (net (code "55") (name "Net-(OI5-A)") (class "Default")
      (node (ref "OI5") (pin "1") (pinfunction "A_1") (pintype "passive"))
      (node (ref "ORIN5") (pin "P$2") (pinfunction "2_P$2") (pintype "passive"))
    )
    (net (code "56") (name "Net-(OI5-COL)") (class "Default")
      (node (ref "OI5") (pin "3") (pinfunction "COL_3") (pintype "passive"))
      (node (ref "RO5A") (pin "2") (pinfunction "2_2") (pintype "passive"))
      (node (ref "RO5B") (pin "1") (pinfunction "1_1") (pintype "passive"))
    )
    (net (code "57") (name "Net-(OI6-A)") (class "Default")
      (node (ref "OI6") (pin "1") (pinfunction "A_1") (pintype "passive"))
      (node (ref "ORIN6") (pin "P$2") (pinfunction "2_P$2") (pintype "passive"))
    )
    (net (code "58") (name "Net-(OI6-COL)") (class "Default")
      (node (ref "OI6") (pin "3") (pinfunction "COL_3") (pintype "passive"))
      (node (ref "RO6A") (pin "2") (pinfunction "2_2") (pintype "passive"))
      (node (ref "RO6B") (pin "1") (pinfunction "1_1") (pintype "passive"))
    )
    (net (code "59") (name "Net-(OI7-A)") (class "Default")
      (node (ref "OI7") (pin "1") (pinfunction "A_1") (pintype "passive"))
      (node (ref "ORIN7") (pin "P$2") (pinfunction "2_P$2") (pintype "passive"))
    )
    (net (code "60") (name "Net-(OI7-COL)") (class "Default")
      (node (ref "OI7") (pin "3") (pinfunction "COL_3") (pintype "passive"))
      (node (ref "RO7A") (pin "2") (pinfunction "2_2") (pintype "passive"))
      (node (ref "RO7B") (pin "1") (pinfunction "1_1") (pintype "passive"))
    )
    (net (code "61") (name "Net-(OI8-A)") (class "Default")
      (node (ref "OI8") (pin "1") (pinfunction "A_1") (pintype "passive"))
      (node (ref "ORIN8") (pin "P$2") (pinfunction "2_P$2") (pintype "passive"))
    )
    (net (code "62") (name "Net-(OI8-COL)") (class "Default")
      (node (ref "OI8") (pin "3") (pinfunction "COL_3") (pintype "passive"))
      (node (ref "RO8A") (pin "2") (pinfunction "2_2") (pintype "passive"))
      (node (ref "RO8B") (pin "1") (pinfunction "1_1") (pintype "passive"))
    )
    (net (code "63") (name "Net-(OI9-A)") (class "Default")
      (node (ref "OI9") (pin "1") (pinfunction "A_1") (pintype "passive"))
      (node (ref "ORIN9") (pin "P$2") (pinfunction "2_P$2") (pintype "passive"))
    )
    (net (code "64") (name "Net-(OI9-COL)") (class "Default")
      (node (ref "OI9") (pin "3") (pinfunction "COL_3") (pintype "passive"))
      (node (ref "RO9A") (pin "2") (pinfunction "2_2") (pintype "passive"))
      (node (ref "RO9B") (pin "1") (pinfunction "1_1") (pintype "passive"))
    )
    (net (code "65") (name "Net-(OI10-A)") (class "Default")
      (node (ref "OI10") (pin "1") (pinfunction "A_1") (pintype "passive"))
      (node (ref "ORIN10") (pin "P$2") (pinfunction "2_P$2") (pintype "passive"))
    )
    (net (code "66") (name "Net-(OI10-COL)") (class "Default")
      (node (ref "OI10") (pin "3") (pinfunction "COL_3") (pintype "passive"))
      (node (ref "RO10A") (pin "2") (pinfunction "2_2") (pintype "passive"))
      (node (ref "RO10B") (pin "1") (pinfunction "1_1") (pintype "passive"))
    )
    (net (code "67") (name "Net-(Q1-IN)") (class "Default")
      (node (ref "Q1") (pin "1") (pinfunction "IN_1") (pintype "input"))
      (node (ref "U$1") (pin "EXTRA23") (pinfunction "EXTRA23_EXTRA23") (pintype "bidirectional"))
    )
    (net (code "68") (name "Net-(Q1-OUT)") (class "Default")
      (node (ref "Q1") (pin "3") (pinfunction "OUT_3") (pintype "output"))
      (node (ref "RO10B") (pin "2") (pinfunction "2_2") (pintype "passive"))
      (node (ref "RO10C") (pin "2") (pinfunction "2_2") (pintype "passive"))
      (node (ref "RO1B") (pin "2") (pinfunction "2_2") (pintype "passive"))
      (node (ref "RO1C") (pin "2") (pinfunction "2_2") (pintype "passive"))
      (node (ref "RO2B") (pin "2") (pinfunction "2_2") (pintype "passive"))
      (node (ref "RO2C") (pin "2") (pinfunction "2_2") (pintype "passive"))
      (node (ref "RO3B") (pin "2") (pinfunction "2_2") (pintype "passive"))
      (node (ref "RO3C") (pin "2") (pinfunction "2_2") (pintype "passive"))
      (node (ref "RO4B") (pin "2") (pinfunction "2_2") (pintype "passive"))
      (node (ref "RO4C") (pin "2") (pinfunction "2_2") (pintype "passive"))
      (node (ref "RO5B") (pin "2") (pinfunction "2_2") (pintype "passive"))
      (node (ref "RO5C") (pin "2") (pinfunction "2_2") (pintype "passive"))
      (node (ref "RO6B") (pin "2") (pinfunction "2_2") (pintype "passive"))
      (node (ref "RO6C") (pin "2") (pinfunction "2_2") (pintype "passive"))
      (node (ref "RO7B") (pin "2") (pinfunction "2_2") (pintype "passive"))
      (node (ref "RO7C") (pin "2") (pinfunction "2_2") (pintype "passive"))
      (node (ref "RO8B") (pin "2") (pinfunction "2_2") (pintype "passive"))
      (node (ref "RO8C") (pin "2") (pinfunction "2_2") (pintype "passive"))
      (node (ref "RO9B") (pin "2") (pinfunction "2_2") (pintype "passive"))
      (node (ref "RO9C") (pin "2") (pinfunction "2_2") (pintype "passive"))
    )
    (net (code "69") (name "Net-(T1-B)") (class "Default")
      (node (ref "RO1A") (pin "1") (pinfunction "1_1") (pintype "passive"))
      (node (ref "T1") (pin "3") (pinfunction "B_3") (pintype "passive"))
    )
    (net (code "70") (name "Net-(T1-C)") (class "Default")
      (node (ref "ESC1") (pin "1") (pinfunction "1_1") (pintype "passive"))
      (node (ref "RO1C") (pin "1") (pinfunction "1_1") (pintype "passive"))
      (node (ref "T1") (pin "2") (pinfunction "C_2") (pintype "passive"))
    )
    (net (code "71") (name "Net-(T2-B)") (class "Default")
      (node (ref "RO2A") (pin "1") (pinfunction "1_1") (pintype "passive"))
      (node (ref "T2") (pin "3") (pinfunction "B_3") (pintype "passive"))
    )
    (net (code "72") (name "Net-(T2-C)") (class "Default")
      (node (ref "ESC2") (pin "1") (pinfunction "1_1") (pintype "passive"))
      (node (ref "RO2C") (pin "1") (pinfunction "1_1") (pintype "passive"))
      (node (ref "T2") (pin "2") (pinfunction "C_2") (pintype "passive"))
    )
    (net (code "73") (name "Net-(T3-B)") (class "Default")
      (node (ref "RO3A") (pin "1") (pinfunction "1_1") (pintype "passive"))
      (node (ref "T3") (pin "3") (pinfunction "B_3") (pintype "passive"))
    )
    (net (code "74") (name "Net-(T3-C)") (class "Default")
      (node (ref "ESC3") (pin "1") (pinfunction "1_1") (pintype "passive"))
      (node (ref "RO3C") (pin "1") (pinfunction "1_1") (pintype "passive"))
      (node (ref "T3") (pin "2") (pinfunction "C_2") (pintype "passive"))
    )
    (net (code "75") (name "Net-(T4-B)") (class "Default")
      (node (ref "RO4A") (pin "1") (pinfunction "1_1") (pintype "passive"))
      (node (ref "T4") (pin "3") (pinfunction "B_3") (pintype "passive"))
    )
    (net (code "76") (name "Net-(T4-C)") (class "Default")
      (node (ref "ESC4") (pin "1") (pinfunction "1_1") (pintype "passive"))
      (node (ref "RO4C") (pin "1") (pinfunction "1_1") (pintype "passive"))
      (node (ref "T4") (pin "2") (pinfunction "C_2") (pintype "passive"))
    )
    (net (code "77") (name "Net-(T5-B)") (class "Default")
      (node (ref "RO5A") (pin "1") (pinfunction "1_1") (pintype "passive"))
      (node (ref "T5") (pin "3") (pinfunction "B_3") (pintype "passive"))
    )
    (net (code "78") (name "Net-(T5-C)") (class "Default")
      (node (ref "ESC5") (pin "1") (pinfunction "1_1") (pintype "passive"))
      (node (ref "RO5C") (pin "1") (pinfunction "1_1") (pintype "passive"))
      (node (ref "T5") (pin "2") (pinfunction "C_2") (pintype "passive"))
    )
    (net (code "79") (name "Net-(T6-B)") (class "Default")
      (node (ref "RO6A") (pin "1") (pinfunction "1_1") (pintype "passive"))
      (node (ref "T6") (pin "3") (pinfunction "B_3") (pintype "passive"))
    )
    (net (code "80") (name "Net-(T6-C)") (class "Default")
      (node (ref "ESC6") (pin "1") (pinfunction "1_1") (pintype "passive"))
      (node (ref "RO6C") (pin "1") (pinfunction "1_1") (pintype "passive"))
      (node (ref "T6") (pin "2") (pinfunction "C_2") (pintype "passive"))
    )
    (net (code "81") (name "Net-(T7-B)") (class "Default")
      (node (ref "RO7A") (pin "1") (pinfunction "1_1") (pintype "passive"))
      (node (ref "T7") (pin "3") (pinfunction "B_3") (pintype "passive"))
    )
    (net (code "82") (name "Net-(T7-C)") (class "Default")
      (node (ref "ESC7") (pin "1") (pinfunction "1_1") (pintype "passive"))
      (node (ref "RO7C") (pin "1") (pinfunction "1_1") (pintype "passive"))
      (node (ref "T7") (pin "2") (pinfunction "C_2") (pintype "passive"))
    )
    (net (code "83") (name "Net-(T8-B)") (class "Default")
      (node (ref "RO8A") (pin "1") (pinfunction "1_1") (pintype "passive"))
      (node (ref "T8") (pin "3") (pinfunction "B_3") (pintype "passive"))
    )
    (net (code "84") (name "Net-(T8-C)") (class "Default")
      (node (ref "ESC8") (pin "1") (pinfunction "1_1") (pintype "passive"))
      (node (ref "RO8C") (pin "1") (pinfunction "1_1") (pintype "passive"))
      (node (ref "T8") (pin "2") (pinfunction "C_2") (pintype "passive"))
    )
    (net (code "85") (name "Net-(T9-B)") (class "Default")
      (node (ref "RO9A") (pin "1") (pinfunction "1_1") (pintype "passive"))
      (node (ref "T9") (pin "3") (pinfunction "B_3") (pintype "passive"))
    )
    (net (code "86") (name "Net-(T9-C)") (class "Default")
      (node (ref "ESC9") (pin "1") (pinfunction "1_1") (pintype "passive"))
      (node (ref "RO9C") (pin "1") (pinfunction "1_1") (pintype "passive"))
      (node (ref "T9") (pin "2") (pinfunction "C_2") (pintype "passive"))
    )
    (net (code "87") (name "Net-(T10-B)") (class "Default")
      (node (ref "RO10A") (pin "1") (pinfunction "1_1") (pintype "passive"))
      (node (ref "T10") (pin "3") (pinfunction "B_3") (pintype "passive"))
    )
    (net (code "88") (name "Net-(T10-C)") (class "Default")
      (node (ref "ESC10") (pin "1") (pinfunction "1_1") (pintype "passive"))
      (node (ref "RO10C") (pin "1") (pinfunction "1_1") (pintype "passive"))
      (node (ref "T10") (pin "2") (pinfunction "C_2") (pintype "passive"))
    )
    (net (code "89") (name "unconnected-(ESC1-Pad2)") (class "Default")
      (node (ref "ESC1") (pin "2") (pinfunction "2_2") (pintype "passive"))
    )
    (net (code "90") (name "unconnected-(ESC2-Pad2)") (class "Default")
      (node (ref "ESC2") (pin "2") (pinfunction "2_2") (pintype "passive"))
    )
    (net (code "91") (name "unconnected-(ESC3-Pad2)") (class "Default")
      (node (ref "ESC3") (pin "2") (pinfunction "2_2") (pintype "passive"))
    )
    (net (code "92") (name "unconnected-(ESC4-Pad2)") (class "Default")
      (node (ref "ESC4") (pin "2") (pinfunction "2_2") (pintype "passive"))
    )
    (net (code "93") (name "unconnected-(ESC5-Pad2)") (class "Default")
      (node (ref "ESC5") (pin "2") (pinfunction "2_2") (pintype "passive"))
    )
    (net (code "94") (name "unconnected-(ESC6-Pad2)") (class "Default")
      (node (ref "ESC6") (pin "2") (pinfunction "2_2") (pintype "passive"))
    )
    (net (code "95") (name "unconnected-(ESC7-Pad2)") (class "Default")
      (node (ref "ESC7") (pin "2") (pinfunction "2_2") (pintype "passive"))
    )
    (net (code "96") (name "unconnected-(ESC8-Pad2)") (class "Default")
      (node (ref "ESC8") (pin "2") (pinfunction "2_2") (pintype "passive"))
    )
    (net (code "97") (name "unconnected-(ESC9-Pad2)") (class "Default")
      (node (ref "ESC9") (pin "2") (pinfunction "2_2") (pintype "passive"))
    )
    (net (code "98") (name "unconnected-(ESC10-Pad2)") (class "Default")
      (node (ref "ESC10") (pin "2") (pinfunction "2_2") (pintype "passive"))
    )
    (net (code "99") (name "unconnected-(IC1-BOOT0-Pad60)") (class "Default")
      (node (ref "IC1") (pin "60") (pinfunction "BOOT0_60") (pintype "passive"))
    )
    (net (code "100") (name "unconnected-(IC1-PA4-Pad20)") (class "Default")
      (node (ref "IC1") (pin "20") (pinfunction "PA4_20") (pintype "passive"))
    )
    (net (code "101") (name "unconnected-(IC1-PA5-Pad21)") (class "Default")
      (node (ref "IC1") (pin "21") (pinfunction "PA5_21") (pintype "passive"))
    )
    (net (code "102") (name "unconnected-(IC1-PA9-Pad42)") (class "Default")
      (node (ref "IC1") (pin "42") (pinfunction "PA9_42") (pintype "passive"))
    )
    (net (code "103") (name "unconnected-(IC1-PA10-Pad43)") (class "Default")
      (node (ref "IC1") (pin "43") (pinfunction "PA10_43") (pintype "passive"))
    )
    (net (code "104") (name "unconnected-(IC1-PA11-Pad44)") (class "Default")
      (node (ref "IC1") (pin "44") (pinfunction "PA11_44") (pintype "passive"))
    )
    (net (code "105") (name "unconnected-(IC1-PA12-Pad45)") (class "Default")
      (node (ref "IC1") (pin "45") (pinfunction "PA12_45") (pintype "passive"))
    )
    (net (code "106") (name "unconnected-(IC1-PB2-Pad28)") (class "Default")
      (node (ref "IC1") (pin "28") (pinfunction "PB2_28") (pintype "passive"))
    )
    (net (code "107") (name "unconnected-(IC1-PB5-Pad57)") (class "Default")
      (node (ref "IC1") (pin "57") (pinfunction "PB5_57") (pintype "passive"))
    )
    (net (code "108") (name "unconnected-(IC1-PB8-Pad61)") (class "Default")
      (node (ref "IC1") (pin "61") (pinfunction "PB8_61") (pintype "passive"))
    )
    (net (code "109") (name "unconnected-(IC1-PB9-Pad62)") (class "Default")
      (node (ref "IC1") (pin "62") (pinfunction "PB9_62") (pintype "passive"))
    )
    (net (code "110") (name "unconnected-(IC1-PB13-Pad34)") (class "Default")
      (node (ref "IC1") (pin "34") (pinfunction "PB13_34") (pintype "passive"))
    )
    (net (code "111") (name "unconnected-(IC1-PC4-Pad24)") (class "Default")
      (node (ref "IC1") (pin "24") (pinfunction "PC4_24") (pintype "passive"))
    )
    (net (code "112") (name "unconnected-(IC1-PC5-Pad25)") (class "Default")
      (node (ref "IC1") (pin "25") (pinfunction "PC5_25") (pintype "passive"))
    )
    (net (code "113") (name "unconnected-(IC1-PC10-Pad51)") (class "Default")
      (node (ref "IC1") (pin "51") (pinfunction "PC10_51") (pintype "passive"))
    )
    (net (code "114") (name "unconnected-(IC1-PC11-Pad52)") (class "Default")
      (node (ref "IC1") (pin "52") (pinfunction "PC11_52") (pintype "passive"))
    )
    (net (code "115") (name "unconnected-(IC1-PC13-Pad2)") (class "Default")
      (node (ref "IC1") (pin "2") (pinfunction "PC13_2") (pintype "passive"))
    )
    (net (code "116") (name "unconnected-(IC1-PC14-Pad3)") (class "Default")
      (node (ref "IC1") (pin "3") (pinfunction "PC14_3") (pintype "passive"))
    )
    (net (code "117") (name "unconnected-(IC1-VBAT-Pad1)") (class "Default")
      (node (ref "IC1") (pin "1") (pinfunction "VBAT_1") (pintype "passive"))
    )
    (net (code "118") (name "unconnected-(J4-Pad11)") (class "Default")
      (node (ref "J4") (pin "11") (pinfunction "11_11") (pintype "passive"))
    )
    (net (code "119") (name "unconnected-(J4-Pad17)") (class "Default")
      (node (ref "J4") (pin "17") (pinfunction "17_17") (pintype "passive"))
    )
    (net (code "120") (name "unconnected-(J4-Pad19)") (class "Default")
      (node (ref "J4") (pin "19") (pinfunction "19_19") (pintype "passive"))
    )
    (net (code "121") (name "unconnected-(J5-CD{slash}DAT3(~{CS})-Pad2)") (class "Default")
      (node (ref "J5") (pin "2") (pinfunction "CD/DAT3(~{CS})_2") (pintype "bidirectional"))
    )
    (net (code "122") (name "unconnected-(J5-DAT1(RSV)-Pad8)") (class "Default")
      (node (ref "J5") (pin "8") (pinfunction "DAT1(RSV)_8") (pintype "bidirectional"))
    )
    (net (code "123") (name "unconnected-(J5-DAT2(NC)-Pad1)") (class "Default")
      (node (ref "J5") (pin "1") (pinfunction "DAT2(NC)_1") (pintype "bidirectional"))
    )
    (net (code "124") (name "unconnected-(J5-PadCD1)") (class "Default")
      (node (ref "J5") (pin "CD1") (pinfunction "CD1_CD1") (pintype "bidirectional"))
    )
    (net (code "125") (name "unconnected-(J5-PadCD2)") (class "Default")
      (node (ref "J5") (pin "CD2") (pinfunction "CD2_CD2") (pintype "bidirectional"))
    )
    (net (code "126") (name "unconnected-(RESET-S-Pad1)") (class "Default")
      (node (ref "RESET") (pin "1") (pinfunction "S_1") (pintype "passive"))
    )
    (net (code "127") (name "unconnected-(U$1-PadCAN_H)") (class "Default")
      (node (ref "U$1") (pin "CAN_H") (pinfunction "CAN_H_CAN_H") (pintype "bidirectional"))
    )
    (net (code "128") (name "unconnected-(U$1-PadCAN_L)") (class "Default")
      (node (ref "U$1") (pin "CAN_L") (pinfunction "CAN_L_CAN_L") (pintype "bidirectional"))
    )
    (net (code "129") (name "unconnected-(U$1-PadEXTRA1)") (class "Default")
      (node (ref "U$1") (pin "EXTRA1") (pinfunction "EXTRA1_EXTRA1") (pintype "bidirectional"))
    )
    (net (code "130") (name "unconnected-(U$1-PadEXTRA2)") (class "Default")
      (node (ref "U$1") (pin "EXTRA2") (pinfunction "EXTRA2_EXTRA2") (pintype "bidirectional"))
    )
    (net (code "131") (name "unconnected-(U$1-PadEXTRA3)") (class "Default")
      (node (ref "U$1") (pin "EXTRA3") (pinfunction "EXTRA3_EXTRA3") (pintype "bidirectional"))
    )
    (net (code "132") (name "unconnected-(U$1-PadEXTRA4)") (class "Default")
      (node (ref "U$1") (pin "EXTRA4") (pinfunction "EXTRA4_EXTRA4") (pintype "bidirectional"))
    )
    (net (code "133") (name "unconnected-(U$1-PadEXTRA5)") (class "Default")
      (node (ref "U$1") (pin "EXTRA5") (pinfunction "EXTRA5_EXTRA5") (pintype "bidirectional"))
    )
    (net (code "134") (name "unconnected-(U$1-PadEXTRA6)") (class "Default")
      (node (ref "U$1") (pin "EXTRA6") (pinfunction "EXTRA6_EXTRA6") (pintype "bidirectional"))
    )
    (net (code "135") (name "unconnected-(U$1-PadEXTRA7)") (class "Default")
      (node (ref "U$1") (pin "EXTRA7") (pinfunction "EXTRA7_EXTRA7") (pintype "bidirectional"))
    )
    (net (code "136") (name "unconnected-(U$1-PadEXTRA8)") (class "Default")
      (node (ref "U$1") (pin "EXTRA8") (pinfunction "EXTRA8_EXTRA8") (pintype "bidirectional"))
    )
    (net (code "137") (name "unconnected-(U$1-PadEXTRA9)") (class "Default")
      (node (ref "U$1") (pin "EXTRA9") (pinfunction "EXTRA9_EXTRA9") (pintype "bidirectional"))
    )
    (net (code "138") (name "unconnected-(U$1-PadEXTRA10)") (class "Default")
      (node (ref "U$1") (pin "EXTRA10") (pinfunction "EXTRA10_EXTRA10") (pintype "bidirectional"))
    )
    (net (code "139") (name "unconnected-(U$1-PadEXTRA11)") (class "Default")
      (node (ref "U$1") (pin "EXTRA11") (pinfunction "EXTRA11_EXTRA11") (pintype "bidirectional"))
    )
    (net (code "140") (name "unconnected-(U$1-PadEXTRA12)") (class "Default")
      (node (ref "U$1") (pin "EXTRA12") (pinfunction "EXTRA12_EXTRA12") (pintype "bidirectional"))
    )
    (net (code "141") (name "unconnected-(U$1-PadEXTRA13)") (class "Default")
      (node (ref "U$1") (pin "EXTRA13") (pinfunction "EXTRA13_EXTRA13") (pintype "bidirectional"))
    )
    (net (code "142") (name "unconnected-(U$1-PadEXTRA14)") (class "Default")
      (node (ref "U$1") (pin "EXTRA14") (pinfunction "EXTRA14_EXTRA14") (pintype "bidirectional"))
    )
    (net (code "143") (name "unconnected-(U$1-PadEXTRA15)") (class "Default")
      (node (ref "U$1") (pin "EXTRA15") (pinfunction "EXTRA15_EXTRA15") (pintype "bidirectional"))
    )
    (net (code "144") (name "unconnected-(U$1-PadEXTRA16)") (class "Default")
      (node (ref "U$1") (pin "EXTRA16") (pinfunction "EXTRA16_EXTRA16") (pintype "bidirectional"))
    )
    (net (code "145") (name "unconnected-(U$1-PadEXTRA17)") (class "Default")
      (node (ref "U$1") (pin "EXTRA17") (pinfunction "EXTRA17_EXTRA17") (pintype "bidirectional"))
    )
    (net (code "146") (name "unconnected-(U$1-PadEXTRA18)") (class "Default")
      (node (ref "U$1") (pin "EXTRA18") (pinfunction "EXTRA18_EXTRA18") (pintype "bidirectional"))
    )
    (net (code "147") (name "unconnected-(U$1-PadEXTRA19)") (class "Default")
      (node (ref "U$1") (pin "EXTRA19") (pinfunction "EXTRA19_EXTRA19") (pintype "bidirectional"))
    )
    (net (code "148") (name "unconnected-(U$1-PadEXTRA20)") (class "Default")
      (node (ref "U$1") (pin "EXTRA20") (pinfunction "EXTRA20_EXTRA20") (pintype "bidirectional"))
    )
    (net (code "149") (name "unconnected-(U$1-PadEXTRA21)") (class "Default")
      (node (ref "U$1") (pin "EXTRA21") (pinfunction "EXTRA21_EXTRA21") (pintype "bidirectional"))
    )
    (net (code "150") (name "unconnected-(U$1-PadEXTRA22)") (class "Default")
      (node (ref "U$1") (pin "EXTRA22") (pinfunction "EXTRA22_EXTRA22") (pintype "bidirectional"))
    )
    (net (code "151") (name "unconnected-(U$1-PadEXTRA25)") (class "Default")
      (node (ref "U$1") (pin "EXTRA25") (pinfunction "EXTRA25_EXTRA25") (pintype "bidirectional"))
    )
    (net (code "152") (name "unconnected-(U$1-PadEXTRA26)") (class "Default")
      (node (ref "U$1") (pin "EXTRA26") (pinfunction "EXTRA26_EXTRA26") (pintype "bidirectional"))
    )
    (net (code "153") (name "unconnected-(U$1-PadEXTRA27)") (class "Default")
      (node (ref "U$1") (pin "EXTRA27") (pinfunction "EXTRA27_EXTRA27") (pintype "bidirectional"))
    )
    (net (code "154") (name "unconnected-(U$1-PadEXTRA28)") (class "Default")
      (node (ref "U$1") (pin "EXTRA28") (pinfunction "EXTRA28_EXTRA28") (pintype "bidirectional"))
    )
    (net (code "155") (name "unconnected-(U$1-PadEXTRA29)") (class "Default")
      (node (ref "U$1") (pin "EXTRA29") (pinfunction "EXTRA29_EXTRA29") (pintype "bidirectional"))
    )
    (net (code "156") (name "unconnected-(U$1-PadEXTRA30)") (class "Default")
      (node (ref "U$1") (pin "EXTRA30") (pinfunction "EXTRA30_EXTRA30") (pintype "bidirectional"))
    )
    (net (code "157") (name "unconnected-(U$1-PadEXTRA31)") (class "Default")
      (node (ref "U$1") (pin "EXTRA31") (pinfunction "EXTRA31_EXTRA31") (pintype "bidirectional"))
    )
    (net (code "158") (name "unconnected-(U$1-PadEXTRA32)") (class "Default")
      (node (ref "U$1") (pin "EXTRA32") (pinfunction "EXTRA32_EXTRA32") (pintype "bidirectional"))
    )
    (net (code "159") (name "unconnected-(U$1-PadEXTRA33)") (class "Default")
      (node (ref "U$1") (pin "EXTRA33") (pinfunction "EXTRA33_EXTRA33") (pintype "bidirectional"))
    )
    (net (code "160") (name "unconnected-(U$1-PadEXTRA34)") (class "Default")
      (node (ref "U$1") (pin "EXTRA34") (pinfunction "EXTRA34_EXTRA34") (pintype "bidirectional"))
    )
    (net (code "161") (name "unconnected-(U$1-PadEXTRA35)") (class "Default")
      (node (ref "U$1") (pin "EXTRA35") (pinfunction "EXTRA35_EXTRA35") (pintype "bidirectional"))
    )
    (net (code "162") (name "unconnected-(U$1-PadSCL_DEPTH)") (class "Default")
      (node (ref "U$1") (pin "SCL_DEPTH") (pinfunction "SCL_DEPTH_SCL_DEPTH") (pintype "bidirectional"))
    )
    (net (code "163") (name "unconnected-(U$1-PadSCL_ESC)") (class "Default")
      (node (ref "U$1") (pin "SCL_ESC") (pinfunction "SCL_ESC_SCL_ESC") (pintype "bidirectional"))
    )
    (net (code "164") (name "unconnected-(U$1-PadSDA_DEPTH)") (class "Default")
      (node (ref "U$1") (pin "SDA_DEPTH") (pinfunction "SDA_DEPTH_SDA_DEPTH") (pintype "bidirectional"))
    )
    (net (code "165") (name "unconnected-(U$1-PadSDA_ESC)") (class "Default")
      (node (ref "U$1") (pin "SDA_ESC") (pinfunction "SDA_ESC_SDA_ESC") (pintype "bidirectional"))
    )
  )
)
